# bs_prod.net
KiCad netlist of a schematic drawn in EAGLE
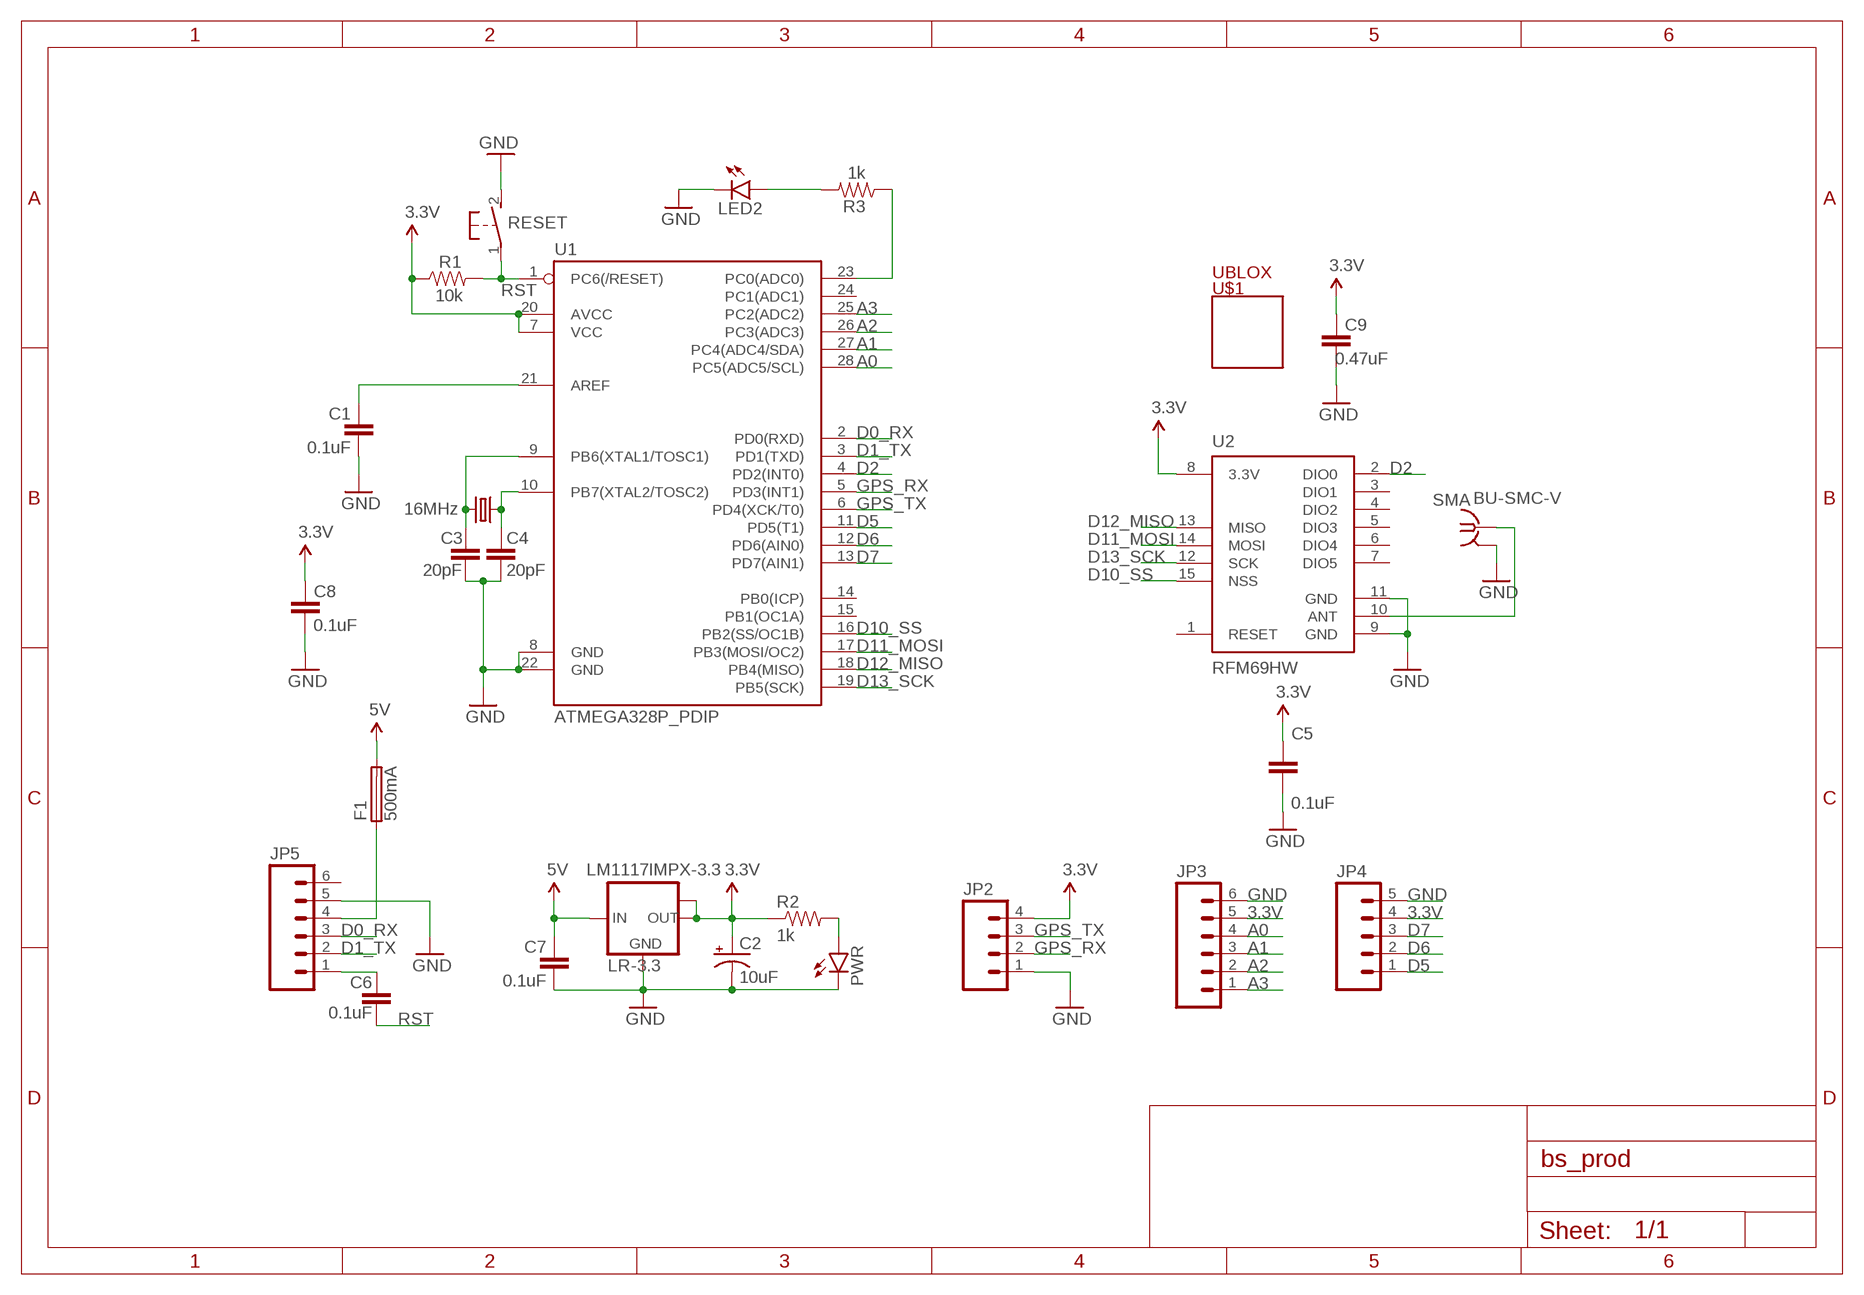
[diagram p0: schematic, sheet 1]

(export (version "E")
  (design (tool "Eeschema 10.0.6"))
  (components
    (comp (ref "C1")
      (value "0.1uF")
      (footprint "eagle-import:1206")
      (libsource (lib "eagle-import") (part "CAP1206"))
    )
    (comp (ref "C2")
      (value "10uF")
      (footprint "eagle-import:PANASONIC_C")
      (libsource (lib "eagle-import") (part "CAP_POLC"))
    )
    (comp (ref "C3")
      (value "20pF")
      (footprint "eagle-import:1206")
      (libsource (lib "eagle-import") (part "CAP1206"))
    )
    (comp (ref "C4")
      (value "20pF")
      (footprint "eagle-import:1206")
      (libsource (lib "eagle-import") (part "CAP1206"))
    )
    (comp (ref "C5")
      (value "0.1uF")
      (footprint "eagle-import:1206")
      (libsource (lib "eagle-import") (part "CAP1206"))
    )
    (comp (ref "C6")
      (value "0.1uF")
      (footprint "eagle-import:1206")
      (libsource (lib "eagle-import") (part "CAP1206"))
    )
    (comp (ref "C7")
      (value "0.1uF")
      (footprint "eagle-import:1206")
      (libsource (lib "eagle-import") (part "CAP1206"))
    )
    (comp (ref "C8")
      (value "0.1uF")
      (footprint "eagle-import:1206")
      (libsource (lib "eagle-import") (part "CAP1206"))
    )
    (comp (ref "C9")
      (value "0.47uF")
      (footprint "eagle-import:1206")
      (libsource (lib "eagle-import") (part "CAP1206"))
    )
    (comp (ref "F1")
      (value "500mA")
      (footprint "eagle-import:TE5")
      (libsource (lib "eagle-import") (part "TE5"))
    )
    (comp (ref "JP2")
      (value "M04PTH")
      (footprint "eagle-import:1X04")
      (libsource (lib "eagle-import") (part "M04PTH"))
    )
    (comp (ref "JP3")
      (value "M06SIP")
      (footprint "eagle-import:1X06")
      (libsource (lib "eagle-import") (part "M06SIP"))
    )
    (comp (ref "JP4")
      (value "M05PTH")
      (footprint "eagle-import:1X05")
      (libsource (lib "eagle-import") (part "M05PTH"))
    )
    (comp (ref "JP5")
      (value "M06SIP")
      (footprint "eagle-import:1X06")
      (libsource (lib "eagle-import") (part "M06SIP"))
    )
    (comp (ref "LED2")
      (value "LED1206")
      (footprint "eagle-import:LED-1206")
      (libsource (lib "eagle-import") (part "LED1206"))
    )
    (comp (ref "LR-3.3")
      (value "LM1117IMPX-3.3")
      (footprint "eagle-import:SOT223")
      (libsource (lib "eagle-import") (part "LM1117IMPX-3.3"))
    )
    (comp (ref "PWR")
      (value "LED1206")
      (footprint "eagle-import:LED-1206")
      (libsource (lib "eagle-import") (part "LED1206"))
    )
    (comp (ref "R1")
      (value "10k")
      (footprint "eagle-import:1206")
      (libsource (lib "eagle-import") (part "RESISTOR1206"))
    )
    (comp (ref "R2")
      (value "1k")
      (footprint "eagle-import:1206")
      (libsource (lib "eagle-import") (part "RESISTOR1206"))
    )
    (comp (ref "R3")
      (value "1k")
      (footprint "eagle-import:1206")
      (libsource (lib "eagle-import") (part "RESISTOR1206"))
    )
    (comp (ref "RESET")
      (value "DTSM-3")
      (footprint "eagle-import:DTSM-3")
      (libsource (lib "eagle-import") (part "DTSM-3"))
    )
    (comp (ref "SMA")
      (value "BU-SMC-V")
      (footprint "eagle-import:BU-SMC-V")
      (libsource (lib "eagle-import") (part "BU-SMC-V"))
    )
    (comp (ref "U$1")
      (value "UBLOX")
      (footprint "eagle-import:UBLOX")
      (libsource (lib "eagle-import") (part "UBLOX"))
    )
    (comp (ref "U1")
      (value "ATMEGA328P_PDIP")
      (footprint "eagle-import:DIL28-3")
      (libsource (lib "eagle-import") (part "ATMEGA328P_PDIP"))
    )
    (comp (ref "U2")
      (value "RFM69HW")
      (footprint "eagle-import:RFM69W-XXXS2")
      (libsource (lib "eagle-import") (part "RFM69HW"))
    )
    (comp (ref "Y1")
      (value "16MHz")
      (footprint "eagle-import:HC49UP")
      (libsource (lib "eagle-import") (part "CRYSTALSMD"))
    )
  )
  (nets
    (net (code "1") (name "/A0") (class "Default")
      (node (ref "JP3") (pin "4") (pinfunction "4_4") (pintype "passive"))
      (node (ref "U1") (pin "28") (pinfunction "PC5(ADC5/SCL)_28") (pintype "bidirectional"))
    )
    (net (code "2") (name "/A1") (class "Default")
      (node (ref "JP3") (pin "3") (pinfunction "3_3") (pintype "passive"))
      (node (ref "U1") (pin "27") (pinfunction "PC4(ADC4/SDA)_27") (pintype "bidirectional"))
    )
    (net (code "3") (name "/A2") (class "Default")
      (node (ref "JP3") (pin "2") (pinfunction "2_2") (pintype "passive"))
      (node (ref "U1") (pin "26") (pinfunction "PC3(ADC3)_26") (pintype "bidirectional"))
    )
    (net (code "4") (name "/A3") (class "Default")
      (node (ref "JP3") (pin "1") (pinfunction "1_1") (pintype "passive"))
      (node (ref "U1") (pin "25") (pinfunction "PC2(ADC2)_25") (pintype "bidirectional"))
    )
    (net (code "5") (name "/D0_RX") (class "Default")
      (node (ref "JP5") (pin "3") (pinfunction "3_3") (pintype "passive"))
      (node (ref "U1") (pin "2") (pinfunction "PD0(RXD)_2") (pintype "bidirectional"))
    )
    (net (code "6") (name "/D1_TX") (class "Default")
      (node (ref "JP5") (pin "2") (pinfunction "2_2") (pintype "passive"))
      (node (ref "U1") (pin "3") (pinfunction "PD1(TXD)_3") (pintype "bidirectional"))
    )
    (net (code "7") (name "/D2") (class "Default")
      (node (ref "U1") (pin "4") (pinfunction "PD2(INT0)_4") (pintype "bidirectional"))
      (node (ref "U2") (pin "2") (pinfunction "DIO0_2") (pintype "bidirectional"))
    )
    (net (code "8") (name "/D5") (class "Default")
      (node (ref "JP4") (pin "1") (pinfunction "1_1") (pintype "passive"))
      (node (ref "U1") (pin "11") (pinfunction "PD5(T1)_11") (pintype "bidirectional"))
    )
    (net (code "9") (name "/D6") (class "Default")
      (node (ref "JP4") (pin "2") (pinfunction "2_2") (pintype "passive"))
      (node (ref "U1") (pin "12") (pinfunction "PD6(AIN0)_12") (pintype "bidirectional"))
    )
    (net (code "10") (name "/D7") (class "Default")
      (node (ref "JP4") (pin "3") (pinfunction "3_3") (pintype "passive"))
      (node (ref "U1") (pin "13") (pinfunction "PD7(AIN1)_13") (pintype "bidirectional"))
    )
    (net (code "11") (name "/D10_SS") (class "Default")
      (node (ref "U1") (pin "16") (pinfunction "PB2(SS/OC1B)_16") (pintype "bidirectional"))
      (node (ref "U2") (pin "15") (pinfunction "NSS_15") (pintype "input"))
    )
    (net (code "12") (name "/D11_MOSI") (class "Default")
      (node (ref "U1") (pin "17") (pinfunction "PB3(MOSI/OC2)_17") (pintype "bidirectional"))
      (node (ref "U2") (pin "14") (pinfunction "MOSI_14") (pintype "input"))
    )
    (net (code "13") (name "/D12_MISO") (class "Default")
      (node (ref "U1") (pin "18") (pinfunction "PB4(MISO)_18") (pintype "bidirectional"))
      (node (ref "U2") (pin "13") (pinfunction "MISO_13") (pintype "bidirectional"))
    )
    (net (code "14") (name "/D13_SCK") (class "Default")
      (node (ref "U1") (pin "19") (pinfunction "PB5(SCK)_19") (pintype "bidirectional"))
      (node (ref "U2") (pin "12") (pinfunction "SCK_12") (pintype "input"))
    )
    (net (code "15") (name "/GPS_RX") (class "Default")
      (node (ref "JP2") (pin "2") (pinfunction "2_2") (pintype "passive"))
      (node (ref "U1") (pin "5") (pinfunction "PD3(INT1)_5") (pintype "bidirectional"))
    )
    (net (code "16") (name "/GPS_TX") (class "Default")
      (node (ref "JP2") (pin "3") (pinfunction "3_3") (pintype "passive"))
      (node (ref "U1") (pin "6") (pinfunction "PD4(XCK/T0)_6") (pintype "bidirectional"))
    )
    (net (code "17") (name "/RST") (class "Default")
      (node (ref "C6") (pin "2") (pinfunction "2_2") (pintype "passive"))
      (node (ref "R1") (pin "2") (pinfunction "2_2") (pintype "passive"))
      (node (ref "RESET") (pin "1") (pinfunction "1_1") (pintype "passive"))
      (node (ref "U1") (pin "1") (pinfunction "PC6(/RESET)_1") (pintype "bidirectional"))
    )
    (net (code "18") (name "3.3V") (class "Default")
      (node (ref "C2") (pin "+") (pinfunction "+_+") (pintype "passive"))
      (node (ref "C5") (pin "1") (pinfunction "1_1") (pintype "passive"))
      (node (ref "C8") (pin "1") (pinfunction "1_1") (pintype "passive"))
      (node (ref "C9") (pin "1") (pinfunction "1_1") (pintype "passive"))
      (node (ref "JP2") (pin "4") (pinfunction "4_4") (pintype "passive"))
      (node (ref "JP3") (pin "5") (pinfunction "5_5") (pintype "passive"))
      (node (ref "JP4") (pin "4") (pinfunction "4_4") (pintype "passive"))
      (node (ref "LR-3.3") (pin "2") (pinfunction "OUT_2") (pintype "passive"))
      (node (ref "LR-3.3") (pin "TAB") (pinfunction "OUT1_TAB") (pintype "passive"))
      (node (ref "R1") (pin "1") (pinfunction "1_1") (pintype "passive"))
      (node (ref "R2") (pin "1") (pinfunction "1_1") (pintype "passive"))
      (node (ref "U1") (pin "20") (pinfunction "AVCC_20") (pintype "bidirectional"))
      (node (ref "U1") (pin "7") (pinfunction "VCC_7") (pintype "bidirectional"))
      (node (ref "U2") (pin "8") (pinfunction "3.3V_8") (pintype "power_in"))
    )
    (net (code "19") (name "5V") (class "Default")
      (node (ref "C7") (pin "1") (pinfunction "1_1") (pintype "passive"))
      (node (ref "F1") (pin "2") (pinfunction "2_2") (pintype "passive"))
      (node (ref "LR-3.3") (pin "3") (pinfunction "IN_3") (pintype "input"))
    )
    (net (code "20") (name "GND") (class "Default")
      (node (ref "C1") (pin "2") (pinfunction "2_2") (pintype "passive"))
      (node (ref "C2") (pin "-") (pinfunction "-_-") (pintype "passive"))
      (node (ref "C3") (pin "2") (pinfunction "2_2") (pintype "passive"))
      (node (ref "C4") (pin "2") (pinfunction "2_2") (pintype "passive"))
      (node (ref "C5") (pin "2") (pinfunction "2_2") (pintype "passive"))
      (node (ref "C7") (pin "2") (pinfunction "2_2") (pintype "passive"))
      (node (ref "C8") (pin "2") (pinfunction "2_2") (pintype "passive"))
      (node (ref "C9") (pin "2") (pinfunction "2_2") (pintype "passive"))
      (node (ref "JP2") (pin "1") (pinfunction "1_1") (pintype "passive"))
      (node (ref "JP3") (pin "6") (pinfunction "6_6") (pintype "passive"))
      (node (ref "JP4") (pin "5") (pinfunction "5_5") (pintype "passive"))
      (node (ref "JP5") (pin "5") (pinfunction "5_5") (pintype "passive"))
      (node (ref "LED2") (pin "C") (pinfunction "C_C") (pintype "passive"))
      (node (ref "LR-3.3") (pin "1") (pinfunction "GND_1") (pintype "input"))
      (node (ref "PWR") (pin "C") (pinfunction "C_C") (pintype "passive"))
      (node (ref "RESET") (pin "2") (pinfunction "2_2") (pintype "passive"))
      (node (ref "SMA") (pin "2") (pinfunction "2_2") (pintype "passive"))
      (node (ref "SMA") (pin "3") (pinfunction "2_3") (pintype "passive"))
      (node (ref "SMA") (pin "4") (pinfunction "2_4") (pintype "passive"))
      (node (ref "SMA") (pin "5") (pinfunction "2_5") (pintype "passive"))
      (node (ref "U1") (pin "22") (pinfunction "GND_22") (pintype "bidirectional"))
      (node (ref "U1") (pin "8") (pinfunction "GND_8") (pintype "bidirectional"))
      (node (ref "U2") (pin "11") (pinfunction "GND_11") (pintype "power_in"))
      (node (ref "U2") (pin "9") (pinfunction "GND_9") (pintype "power_in"))
    )
    (net (code "21") (name "Net-(C6-Pad1)") (class "Default")
      (node (ref "C6") (pin "1") (pinfunction "1_1") (pintype "passive"))
      (node (ref "JP5") (pin "1") (pinfunction "1_1") (pintype "passive"))
    )
    (net (code "22") (name "Net-(F1-Pad1)") (class "Default")
      (node (ref "F1") (pin "1") (pinfunction "1_1") (pintype "passive"))
      (node (ref "JP5") (pin "4") (pinfunction "4_4") (pintype "passive"))
    )
    (net (code "23") (name "Net-(LED2-PadA)") (class "Default")
      (node (ref "LED2") (pin "A") (pinfunction "A_A") (pintype "passive"))
      (node (ref "R3") (pin "2") (pinfunction "2_2") (pintype "passive"))
    )
    (net (code "24") (name "Net-(PWR-PadA)") (class "Default")
      (node (ref "PWR") (pin "A") (pinfunction "A_A") (pintype "passive"))
      (node (ref "R2") (pin "2") (pinfunction "2_2") (pintype "passive"))
    )
    (net (code "25") (name "Net-(U1-AREF)") (class "Default")
      (node (ref "C1") (pin "1") (pinfunction "1_1") (pintype "passive"))
      (node (ref "U1") (pin "21") (pinfunction "AREF_21") (pintype "bidirectional"))
    )
    (net (code "26") (name "Net-(U1-PB6(XTAL1{slash}TOSC1))") (class "Default")
      (node (ref "C3") (pin "1") (pinfunction "1_1") (pintype "passive"))
      (node (ref "U1") (pin "9") (pinfunction "PB6(XTAL1/TOSC1)_9") (pintype "bidirectional"))
      (node (ref "Y1") (pin "2") (pinfunction "2_2") (pintype "passive"))
    )
    (net (code "27") (name "Net-(U1-PB7(XTAL2{slash}TOSC2))") (class "Default")
      (node (ref "C4") (pin "1") (pinfunction "1_1") (pintype "passive"))
      (node (ref "U1") (pin "10") (pinfunction "PB7(XTAL2/TOSC2)_10") (pintype "bidirectional"))
      (node (ref "Y1") (pin "1") (pinfunction "1_1") (pintype "passive"))
    )
    (net (code "28") (name "Net-(U1-PC0(ADC0))") (class "Default")
      (node (ref "R3") (pin "1") (pinfunction "1_1") (pintype "passive"))
      (node (ref "U1") (pin "23") (pinfunction "PC0(ADC0)_23") (pintype "bidirectional"))
    )
    (net (code "29") (name "Net-(U2-ANT)") (class "Default")
      (node (ref "SMA") (pin "1") (pinfunction "1_1") (pintype "passive"))
      (node (ref "U2") (pin "10") (pinfunction "ANT_10") (pintype "passive"))
    )
    (net (code "30") (name "unconnected-(JP5-Pad6)") (class "Default")
      (node (ref "JP5") (pin "6") (pinfunction "6_6") (pintype "passive"))
    )
    (net (code "31") (name "unconnected-(U1-PB0(ICP)-Pad14)") (class "Default")
      (node (ref "U1") (pin "14") (pinfunction "PB0(ICP)_14") (pintype "bidirectional"))
    )
    (net (code "32") (name "unconnected-(U1-PB1(OC1A)-Pad15)") (class "Default")
      (node (ref "U1") (pin "15") (pinfunction "PB1(OC1A)_15") (pintype "bidirectional"))
    )
    (net (code "33") (name "unconnected-(U1-PC1(ADC1)-Pad24)") (class "Default")
      (node (ref "U1") (pin "24") (pinfunction "PC1(ADC1)_24") (pintype "bidirectional"))
    )
    (net (code "34") (name "unconnected-(U2-DIO1-Pad3)") (class "Default")
      (node (ref "U2") (pin "3") (pinfunction "DIO1_3") (pintype "bidirectional"))
    )
    (net (code "35") (name "unconnected-(U2-DIO2-Pad4)") (class "Default")
      (node (ref "U2") (pin "4") (pinfunction "DIO2_4") (pintype "bidirectional"))
    )
    (net (code "36") (name "unconnected-(U2-DIO3-Pad5)") (class "Default")
      (node (ref "U2") (pin "5") (pinfunction "DIO3_5") (pintype "bidirectional"))
    )
    (net (code "37") (name "unconnected-(U2-DIO4-Pad6)") (class "Default")
      (node (ref "U2") (pin "6") (pinfunction "DIO4_6") (pintype "bidirectional"))
    )
    (net (code "38") (name "unconnected-(U2-DIO5-Pad7)") (class "Default")
      (node (ref "U2") (pin "7") (pinfunction "DIO5_7") (pintype "bidirectional"))
    )
    (net (code "39") (name "unconnected-(U2-RESET-Pad1)") (class "Default")
      (node (ref "U2") (pin "1") (pinfunction "RESET_1") (pintype "input"))
    )
  )
)
